# ESP8266.net
KiCad netlist of a schematic drawn in Altium Designer
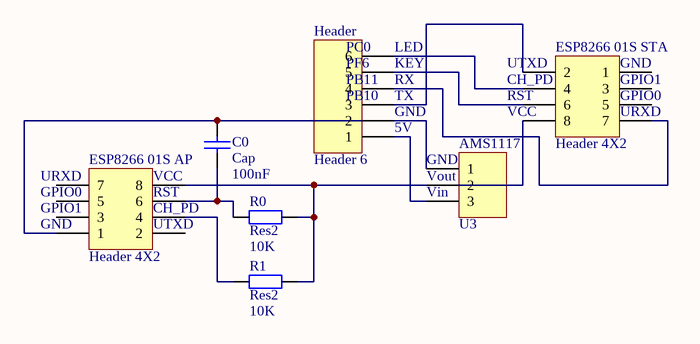
[diagram p0: ESP8266.SchDoc]

(export (version "E")
  (design (tool "Eeschema 10.0.6"))
  (components
    (comp (ref "AMS1117")
      (value "U3")
      (footprint "HDR1X3")
      (description "Header, 3-Pin")
      (fields (field (name "PUBLISHER") "Altium Limited"))
      (libsource (lib "Miscellaneous Connectors") (part "Header 3"))
    )
    (comp (ref "C0")
      (value "Cap")
      (footprint "RAD-0.3")
      (description "Capacitor")
      (fields (field (name "ALTIUM_VALUE") "100nF") (field (name "PUBLISHER") "Altium Limited"))
      (libsource (lib "Miscellaneous Devices") (part "Cap"))
    )
    (comp (ref "ESP8266 01S AP")
      (value "Header 4X2")
      (footprint "HDR2X4")
      (description "Header, 4-Pin, Dual row")
      (fields (field (name "PUBLISHER") "Altium Limited"))
      (libsource (lib "Miscellaneous Connectors") (part "Header 4X2"))
    )
    (comp (ref "ESP8266 01S STA")
      (value "Header 4X2")
      (footprint "HDR2X4")
      (description "Header, 4-Pin, Dual row")
      (fields (field (name "PUBLISHER") "Altium Limited"))
      (libsource (lib "") (part "Header 4X2_1"))
    )
    (comp (ref "Header")
      (value "Header 6")
      (footprint "HDR1X6")
      (description "Header, 6-Pin")
      (fields (field (name "PUBLISHER") "Altium Limited"))
      (libsource (lib "Miscellaneous Connectors") (part "Header 6"))
    )
    (comp (ref "R0")
      (value "Res2")
      (footprint "AXIAL-0.4")
      (description "Resistor")
      (fields (field (name "ALTIUM_VALUE") "10K") (field (name "PUBLISHER") "Altium Limited"))
      (libsource (lib "Miscellaneous Devices") (part "Res2"))
    )
    (comp (ref "R1")
      (value "Res2")
      (footprint "AXIAL-0.4")
      (description "Resistor")
      (fields (field (name "ALTIUM_VALUE") "10K") (field (name "PUBLISHER") "Altium Limited"))
      (libsource (lib "Miscellaneous Devices") (part "Res2"))
    )
  )
  (nets
    (net (code "1") (name "Net-(AMS1117-Pad1)") (class "Default")
      (node (ref "AMS1117") (pin "1") (pinfunction "1_1") (pintype "passive"))
      (node (ref "Header") (pin "2") (pinfunction "2_2") (pintype "passive"))
    )
    (net (code "2") (name "Net-(AMS1117-Pad2)") (class "Default")
      (node (ref "AMS1117") (pin "2") (pinfunction "2_2") (pintype "passive"))
      (node (ref "ESP8266 01S AP") (pin "8") (pinfunction "8_8") (pintype "passive"))
      (node (ref "R0") (pin "2") (pinfunction "2_2") (pintype "passive"))
      (node (ref "R1") (pin "2") (pinfunction "2_2") (pintype "passive"))
    )
    (net (code "3") (name "Net-(AMS1117-Pad3)") (class "Default")
      (node (ref "AMS1117") (pin "3") (pinfunction "3_3") (pintype "passive"))
      (node (ref "Header") (pin "1") (pinfunction "1_1") (pintype "passive"))
    )
    (net (code "4") (name "Net-(C0-Pad1)") (class "Default")
      (node (ref "C0") (pin "1") (pinfunction "1_1") (pintype "passive"))
      (node (ref "ESP8266 01S AP") (pin "6") (pinfunction "6_6") (pintype "passive"))
      (node (ref "R0") (pin "1") (pinfunction "1_1") (pintype "passive"))
    )
    (net (code "5") (name "Net-(C0-Pad2)") (class "Default")
      (node (ref "C0") (pin "2") (pinfunction "2_2") (pintype "passive"))
      (node (ref "ESP8266 01S AP") (pin "1") (pinfunction "1_1") (pintype "passive"))
    )
    (net (code "6") (name "Net-(ESP8266 01S AP-Pad4)") (class "Default")
      (node (ref "ESP8266 01S AP") (pin "4") (pinfunction "4_4") (pintype "passive"))
      (node (ref "R1") (pin "1") (pinfunction "1_1") (pintype "passive"))
    )
    (net (code "7") (name "Net-(ESP8266 01S STA-Pad2)") (class "Default")
      (node (ref "ESP8266 01S STA") (pin "2") (pinfunction "2_2") (pintype "passive"))
      (node (ref "Header") (pin "3") (pinfunction "3_3") (pintype "passive"))
    )
    (net (code "8") (name "Net-(ESP8266 01S STA-Pad4)") (class "Default")
      (node (ref "ESP8266 01S STA") (pin "4") (pinfunction "4_4") (pintype "passive"))
      (node (ref "Header") (pin "6") (pinfunction "6_6") (pintype "passive"))
    )
    (net (code "9") (name "Net-(ESP8266 01S STA-Pad6)") (class "Default")
      (node (ref "ESP8266 01S STA") (pin "6") (pinfunction "6_6") (pintype "passive"))
      (node (ref "Header") (pin "5") (pinfunction "5_5") (pintype "passive"))
    )
    (net (code "10") (name "Net-(ESP8266 01S STA-Pad7)") (class "Default")
      (node (ref "ESP8266 01S STA") (pin "7") (pinfunction "7_7") (pintype "passive"))
      (node (ref "Header") (pin "4") (pinfunction "4_4") (pintype "passive"))
    )
    (net (code "11") (name "unconnected-(ESP8266 01S AP-Pad2)") (class "Default")
      (node (ref "ESP8266 01S AP") (pin "2") (pinfunction "2_2") (pintype "passive"))
    )
    (net (code "12") (name "unconnected-(ESP8266 01S AP-Pad3)") (class "Default")
      (node (ref "ESP8266 01S AP") (pin "3") (pinfunction "3_3") (pintype "passive"))
    )
    (net (code "13") (name "unconnected-(ESP8266 01S AP-Pad5)") (class "Default")
      (node (ref "ESP8266 01S AP") (pin "5") (pinfunction "5_5") (pintype "passive"))
    )
    (net (code "14") (name "unconnected-(ESP8266 01S AP-Pad7)") (class "Default")
      (node (ref "ESP8266 01S AP") (pin "7") (pinfunction "7_7") (pintype "passive"))
    )
    (net (code "15") (name "unconnected-(ESP8266 01S STA-Pad1)") (class "Default")
      (node (ref "ESP8266 01S STA") (pin "1") (pinfunction "1_1") (pintype "passive"))
    )
    (net (code "16") (name "unconnected-(ESP8266 01S STA-Pad3)") (class "Default")
      (node (ref "ESP8266 01S STA") (pin "3") (pinfunction "3_3") (pintype "passive"))
    )
    (net (code "17") (name "unconnected-(ESP8266 01S STA-Pad5)") (class "Default")
      (node (ref "ESP8266 01S STA") (pin "5") (pinfunction "5_5") (pintype "passive"))
    )
    (net (code "18") (name "unconnected-(ESP8266 01S STA-Pad8)") (class "Default")
      (node (ref "ESP8266 01S STA") (pin "8") (pinfunction "8_8") (pintype "passive"))
    )
  )
)
